# Low_Current_Sense.net
KiCad netlist of a schematic drawn in Altium Designer
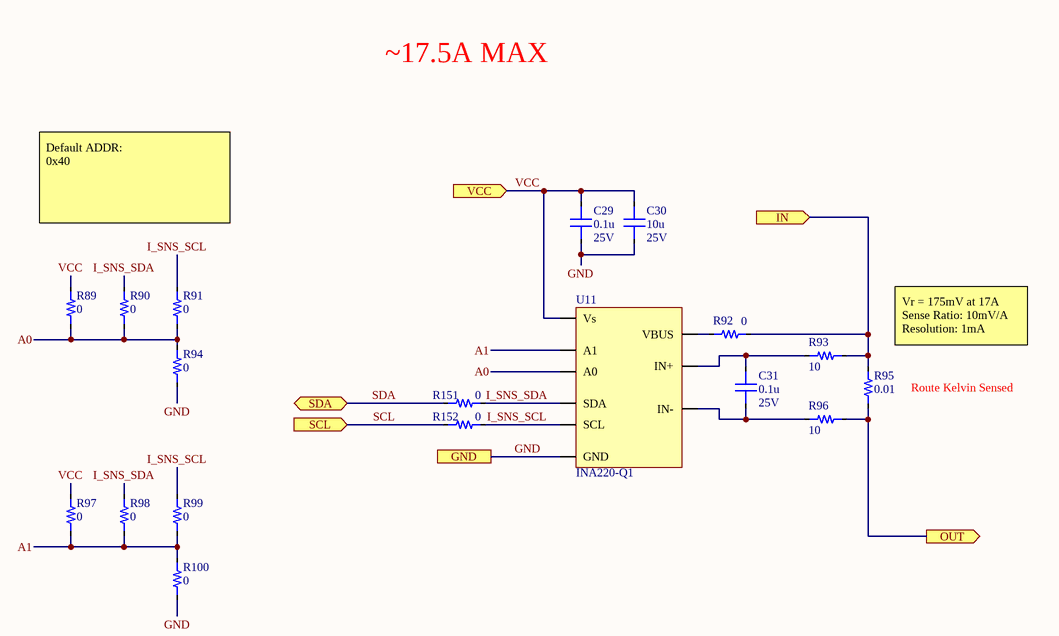
[diagram p0: Low_Current_Sense.SchDoc]

(export (version "E")
  (design (tool "Eeschema 10.0.6"))
  (components
    (comp (ref "C29")
      (value "0.1u")
      (footprint "0603_CAP")
      (fields (field (name "VOLTAGE") "25V") (field (name "Comment") "Capacitor"))
      (libsource (lib "Capacitors") (part "Capacitor"))
    )
    (comp (ref "C30")
      (value "10u")
      (footprint "0805_CAP")
      (fields (field (name "VOLTAGE") "25V") (field (name "Comment") "Capacitor"))
      (libsource (lib "Capacitors") (part "Capacitor"))
    )
    (comp (ref "C31")
      (value "0.1u")
      (footprint "0603_CAP")
      (fields (field (name "VOLTAGE") "25V") (field (name "Comment") "Capacitor"))
      (libsource (lib "Capacitors") (part "Capacitor"))
    )
    (comp (ref "R89")
      (value "0")
      (footprint "0603_RES")
      (fields (field (name "Comment") "Resistor"))
      (libsource (lib "Resistors") (part "Resistor"))
    )
    (comp (ref "R90")
      (value "0")
      (footprint "0603_RES")
      (fields (field (name "Comment") "Resistor"))
      (libsource (lib "Resistors") (part "Resistor"))
    )
    (comp (ref "R91")
      (value "0")
      (footprint "0603_RES")
      (fields (field (name "Comment") "Resistor"))
      (libsource (lib "Resistors") (part "Resistor"))
    )
    (comp (ref "R92")
      (value "0")
      (footprint "0603_RES")
      (fields (field (name "Comment") "Resistor"))
      (libsource (lib "Resistors") (part "Resistor"))
    )
    (comp (ref "R93")
      (value "10")
      (footprint "0603_RES")
      (fields (field (name "Comment") "Resistor"))
      (libsource (lib "Resistors") (part "Resistor"))
    )
    (comp (ref "R94")
      (value "0")
      (footprint "0603_RES")
      (fields (field (name "Comment") "Resistor"))
      (libsource (lib "Resistors") (part "Resistor"))
    )
    (comp (ref "R95")
      (value "0.01")
      (footprint "2512_RES")
      (fields (field (name "TOLERANCE") "1%") (field (name "POWER") "3") (field (name "Comment") "Resistor"))
      (libsource (lib "Resistors") (part "Resistor"))
    )
    (comp (ref "R96")
      (value "10")
      (footprint "0603_RES")
      (fields (field (name "Comment") "Resistor"))
      (libsource (lib "Resistors") (part "Resistor"))
    )
    (comp (ref "R97")
      (value "0")
      (footprint "0603_RES")
      (fields (field (name "Comment") "Resistor"))
      (libsource (lib "Resistors") (part "Resistor"))
    )
    (comp (ref "R98")
      (value "0")
      (footprint "0603_RES")
      (fields (field (name "Comment") "Resistor"))
      (libsource (lib "Resistors") (part "Resistor"))
    )
    (comp (ref "R99")
      (value "0")
      (footprint "0603_RES")
      (fields (field (name "Comment") "Resistor"))
      (libsource (lib "Resistors") (part "Resistor"))
    )
    (comp (ref "R100")
      (value "0")
      (footprint "0603_RES")
      (fields (field (name "Comment") "Resistor"))
      (libsource (lib "Resistors") (part "Resistor"))
    )
    (comp (ref "R151")
      (value "0")
      (footprint "0603_RES")
      (fields (field (name "Comment") "Resistor"))
      (libsource (lib "Resistors") (part "Resistor"))
    )
    (comp (ref "R152")
      (value "0")
      (footprint "0603_RES")
      (fields (field (name "Comment") "Resistor"))
      (libsource (lib "Resistors") (part "Resistor"))
    )
    (comp (ref "U11")
      (value "INA220-Q1")
      (footprint "TSSOP-10")
      (description "Current Monitor Regulator High/Low-Side 10mA 10-VSSOP")
      (libsource (lib "Analog_IC") (part "INA220-Q1"))
    )
  )
  (nets
    (net (code "1") (name "/A0") (class "Default")
      (node (ref "R89") (pin "1") (pinfunction "1_1") (pintype "passive"))
      (node (ref "R90") (pin "1") (pinfunction "1_1") (pintype "passive"))
      (node (ref "R91") (pin "1") (pinfunction "1_1") (pintype "passive"))
      (node (ref "R94") (pin "2") (pinfunction "2_2") (pintype "passive"))
      (node (ref "U11") (pin "2") (pinfunction "A0_2") (pintype "passive"))
    )
    (net (code "2") (name "/A1") (class "Default")
      (node (ref "R100") (pin "2") (pinfunction "2_2") (pintype "passive"))
      (node (ref "R97") (pin "1") (pinfunction "1_1") (pintype "passive"))
      (node (ref "R98") (pin "1") (pinfunction "1_1") (pintype "passive"))
      (node (ref "R99") (pin "1") (pinfunction "1_1") (pintype "passive"))
      (node (ref "U11") (pin "1") (pinfunction "A1_1") (pintype "passive"))
    )
    (net (code "3") (name "/GND") (class "Default")
      (node (ref "C29") (pin "1") (pinfunction "1_1") (pintype "passive"))
      (node (ref "C30") (pin "1") (pinfunction "1_1") (pintype "passive"))
      (node (ref "R100") (pin "1") (pinfunction "1_1") (pintype "passive"))
      (node (ref "R94") (pin "1") (pinfunction "1_1") (pintype "passive"))
      (node (ref "U11") (pin "7") (pinfunction "GND_7") (pintype "passive"))
    )
    (net (code "4") (name "/IN") (class "Default")
      (node (ref "R92") (pin "2") (pinfunction "2_2") (pintype "passive"))
      (node (ref "R93") (pin "2") (pinfunction "2_2") (pintype "passive"))
      (node (ref "R95") (pin "2") (pinfunction "2_2") (pintype "passive"))
    )
    (net (code "5") (name "/I_SNS_SCL") (class "Default")
      (node (ref "R152") (pin "2") (pinfunction "2_2") (pintype "passive"))
      (node (ref "R91") (pin "2") (pinfunction "2_2") (pintype "passive"))
      (node (ref "R99") (pin "2") (pinfunction "2_2") (pintype "passive"))
      (node (ref "U11") (pin "5") (pinfunction "SCL_5") (pintype "passive"))
    )
    (net (code "6") (name "/I_SNS_SDA") (class "Default")
      (node (ref "R151") (pin "2") (pinfunction "2_2") (pintype "passive"))
      (node (ref "R90") (pin "2") (pinfunction "2_2") (pintype "passive"))
      (node (ref "R98") (pin "2") (pinfunction "2_2") (pintype "passive"))
      (node (ref "U11") (pin "4") (pinfunction "SDA_4") (pintype "passive"))
    )
    (net (code "7") (name "/OUT") (class "Default")
      (node (ref "R95") (pin "1") (pinfunction "1_1") (pintype "passive"))
      (node (ref "R96") (pin "2") (pinfunction "2_2") (pintype "passive"))
    )
    (net (code "8") (name "/SCL") (class "Default")
      (node (ref "R152") (pin "1") (pinfunction "1_1") (pintype "passive"))
    )
    (net (code "9") (name "/SDA") (class "Default")
      (node (ref "R151") (pin "1") (pinfunction "1_1") (pintype "passive"))
    )
    (net (code "10") (name "/VCC") (class "Default")
      (node (ref "C29") (pin "2") (pinfunction "2_2") (pintype "passive"))
      (node (ref "C30") (pin "2") (pinfunction "2_2") (pintype "passive"))
      (node (ref "R89") (pin "2") (pinfunction "2_2") (pintype "passive"))
      (node (ref "R97") (pin "2") (pinfunction "2_2") (pintype "passive"))
      (node (ref "U11") (pin "6") (pinfunction "Vs_6") (pintype "passive"))
    )
    (net (code "11") (name "Net-(U11-IN+)") (class "Default")
      (node (ref "C31") (pin "2") (pinfunction "2_2") (pintype "passive"))
      (node (ref "R93") (pin "1") (pinfunction "1_1") (pintype "passive"))
      (node (ref "U11") (pin "10") (pinfunction "IN+_10") (pintype "passive"))
    )
    (net (code "12") (name "Net-(U11-IN-)") (class "Default")
      (node (ref "C31") (pin "1") (pinfunction "1_1") (pintype "passive"))
      (node (ref "R96") (pin "1") (pinfunction "1_1") (pintype "passive"))
      (node (ref "U11") (pin "9") (pinfunction "IN-_9") (pintype "passive"))
    )
    (net (code "13") (name "Net-(U11-VBUS)") (class "Default")
      (node (ref "R92") (pin "1") (pinfunction "1_1") (pintype "passive"))
      (node (ref "U11") (pin "8") (pinfunction "VBUS_8") (pintype "passive"))
    )
  )
)
